# BOB.net
KiCad netlist of a schematic drawn in Altium Designer
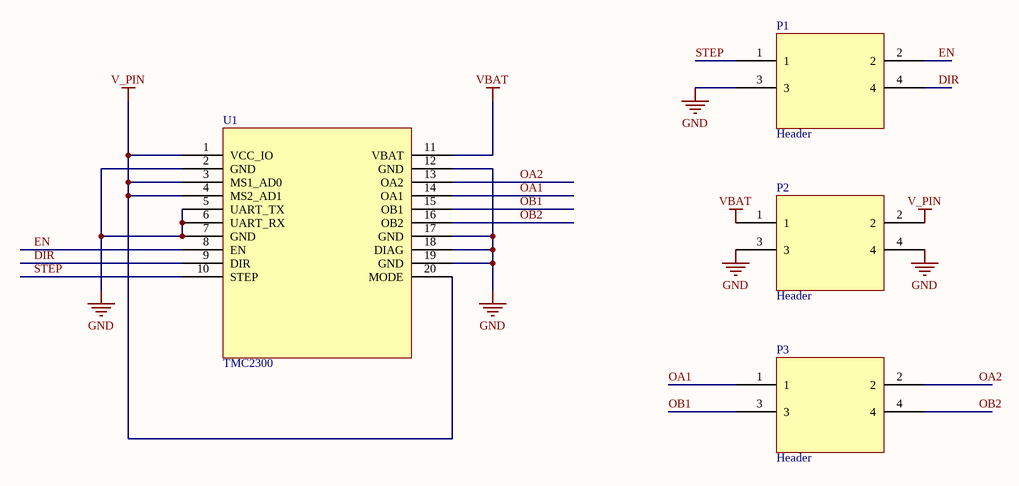
[diagram p0: BOB.SchDoc]

(export (version "E")
  (design (tool "Eeschema 10.0.6"))
  (components
    (comp (ref "P1") (value "Header") (footprint "Connector") (libsource (lib "BOB") (part "Component_2")))
    (comp (ref "P2") (value "Header") (footprint "Connector") (libsource (lib "BOB") (part "Component_2")))
    (comp (ref "P3") (value "Header") (footprint "Connector") (libsource (lib "BOB") (part "Component_2")))
    (comp (ref "U1") (value "TMC2300") (footprint "BOB") (libsource (lib "BOB") (part "Component_1")))
  )
  (nets
    (net (code "1") (name "/DIR") (class "Default")
      (node (ref "P1") (pin "4") (pinfunction "4_4") (pintype "passive"))
      (node (ref "U1") (pin "9") (pinfunction "DIR_9") (pintype "passive"))
    )
    (net (code "2") (name "/EN") (class "Default")
      (node (ref "P1") (pin "2") (pinfunction "2_2") (pintype "passive"))
      (node (ref "U1") (pin "8") (pinfunction "EN_8") (pintype "passive"))
    )
    (net (code "3") (name "/OA1") (class "Default")
      (node (ref "P3") (pin "1") (pinfunction "1_1") (pintype "passive"))
      (node (ref "U1") (pin "14") (pinfunction "OA1_14") (pintype "passive"))
    )
    (net (code "4") (name "/OA2") (class "Default")
      (node (ref "P3") (pin "2") (pinfunction "2_2") (pintype "passive"))
      (node (ref "U1") (pin "13") (pinfunction "OA2_13") (pintype "passive"))
    )
    (net (code "5") (name "/OB1") (class "Default")
      (node (ref "P3") (pin "3") (pinfunction "3_3") (pintype "passive"))
      (node (ref "U1") (pin "15") (pinfunction "OB1_15") (pintype "passive"))
    )
    (net (code "6") (name "/OB2") (class "Default")
      (node (ref "P3") (pin "4") (pinfunction "4_4") (pintype "passive"))
      (node (ref "U1") (pin "16") (pinfunction "OB2_16") (pintype "passive"))
    )
    (net (code "7") (name "/STEP") (class "Default")
      (node (ref "P1") (pin "1") (pinfunction "1_1") (pintype "passive"))
      (node (ref "U1") (pin "10") (pinfunction "STEP_10") (pintype "passive"))
    )
    (net (code "8") (name "GND") (class "Default")
      (node (ref "P1") (pin "3") (pinfunction "3_3") (pintype "passive"))
      (node (ref "P2") (pin "3") (pinfunction "3_3") (pintype "passive"))
      (node (ref "P2") (pin "4") (pinfunction "4_4") (pintype "passive"))
      (node (ref "U1") (pin "12") (pinfunction "GND_12") (pintype "passive"))
      (node (ref "U1") (pin "17") (pinfunction "GND_17") (pintype "passive"))
      (node (ref "U1") (pin "18") (pinfunction "DIAG_18") (pintype "passive"))
      (node (ref "U1") (pin "19") (pinfunction "GND_19") (pintype "passive"))
      (node (ref "U1") (pin "2") (pinfunction "GND_2") (pintype "passive"))
      (node (ref "U1") (pin "5") (pinfunction "UART_TX_5") (pintype "passive"))
      (node (ref "U1") (pin "6") (pinfunction "UART_RX_6") (pintype "passive"))
      (node (ref "U1") (pin "7") (pinfunction "GND_7") (pintype "passive"))
    )
    (net (code "9") (name "VBAT") (class "Default")
      (node (ref "P2") (pin "1") (pinfunction "1_1") (pintype "passive"))
      (node (ref "U1") (pin "11") (pinfunction "VBAT_11") (pintype "passive"))
    )
    (net (code "10") (name "V_PIN") (class "Default")
      (node (ref "P2") (pin "2") (pinfunction "2_2") (pintype "passive"))
      (node (ref "U1") (pin "1") (pinfunction "VCC_IO_1") (pintype "passive"))
      (node (ref "U1") (pin "20") (pinfunction "MODE_20") (pintype "passive"))
      (node (ref "U1") (pin "3") (pinfunction "MS1_AD0_3") (pintype "passive"))
      (node (ref "U1") (pin "4") (pinfunction "MS2_AD1_4") (pintype "passive"))
    )
  )
)
